# GPU_11_Bit_Counter.net
KiCad netlist of a schematic drawn in EAGLE
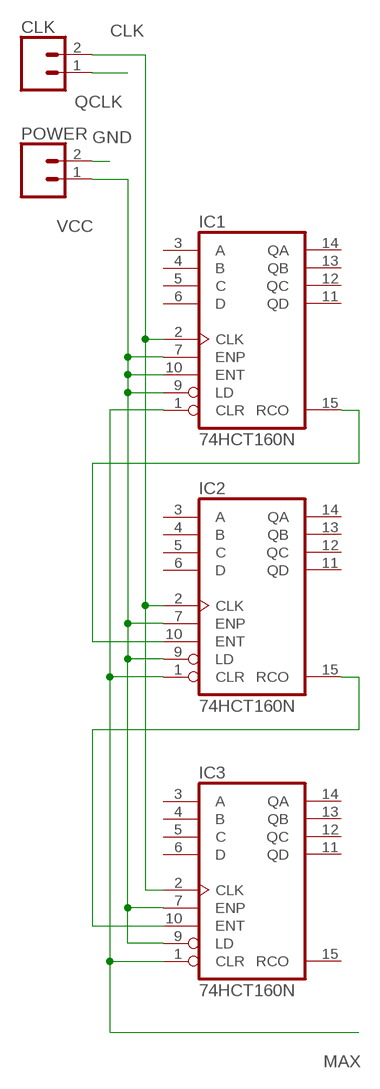
[diagram p0: schematic, sheet 1]

(export (version "E")
  (design (tool "Eeschema 10.0.6"))
  (components
    (comp (ref "CLK")
      (value "CONN_02POGO_PIN_HOLES_ONLY")
      (footprint "eagle-import:1X02_PP_HOLES_ONLY")
      (libsource (lib "eagle-import") (part "CONN_02POGO_PIN_HOLES_ONLY"))
    )
    (comp (ref "IC1")
      (value "74HCT160N")
      (footprint "eagle-import:DIL16")
      (libsource (lib "eagle-import") (part "74160NHCT"))
    )
    (comp (ref "IC2")
      (value "74HCT160N")
      (footprint "eagle-import:DIL16")
      (libsource (lib "eagle-import") (part "74160NHCT"))
    )
    (comp (ref "IC3")
      (value "74HCT160N")
      (footprint "eagle-import:DIL16")
      (libsource (lib "eagle-import") (part "74160NHCT"))
    )
    (comp (ref "POWER")
      (value "CONN_02POGO_PIN_HOLES_ONLY")
      (footprint "eagle-import:1X02_PP_HOLES_ONLY")
      (libsource (lib "eagle-import") (part "CONN_02POGO_PIN_HOLES_ONLY"))
    )
  )
  (nets
    (net (code "1") (name "/CLK") (class "Default")
      (node (ref "CLK") (pin "2") (pinfunction "2_2") (pintype "passive"))
      (node (ref "IC1") (pin "2") (pinfunction "CLK_2") (pintype "input"))
      (node (ref "IC2") (pin "2") (pinfunction "CLK_2") (pintype "input"))
      (node (ref "IC3") (pin "2") (pinfunction "CLK_2") (pintype "input"))
    )
    (net (code "2") (name "/GND") (class "Default")
      (node (ref "POWER") (pin "2") (pinfunction "2_2") (pintype "passive"))
    )
    (net (code "3") (name "/MAX") (class "Default")
      (node (ref "IC1") (pin "1") (pinfunction "CLR_1") (pintype "input"))
      (node (ref "IC2") (pin "1") (pinfunction "CLR_1") (pintype "input"))
      (node (ref "IC3") (pin "1") (pinfunction "CLR_1") (pintype "input"))
    )
    (net (code "4") (name "/QCLK") (class "Default")
      (node (ref "CLK") (pin "1") (pinfunction "1_1") (pintype "passive"))
    )
    (net (code "5") (name "/VCC") (class "Default")
      (node (ref "IC1") (pin "10") (pinfunction "ENT_10") (pintype "input"))
      (node (ref "IC1") (pin "7") (pinfunction "ENP_7") (pintype "input"))
      (node (ref "IC1") (pin "9") (pinfunction "LD_9") (pintype "input"))
      (node (ref "IC2") (pin "7") (pinfunction "ENP_7") (pintype "input"))
      (node (ref "IC2") (pin "9") (pinfunction "LD_9") (pintype "input"))
      (node (ref "IC3") (pin "7") (pinfunction "ENP_7") (pintype "input"))
      (node (ref "IC3") (pin "9") (pinfunction "LD_9") (pintype "input"))
      (node (ref "POWER") (pin "1") (pinfunction "1_1") (pintype "passive"))
    )
    (net (code "6") (name "Net-(IC1A-RCO)") (class "Default")
      (node (ref "IC1") (pin "15") (pinfunction "RCO_15") (pintype "output"))
      (node (ref "IC2") (pin "10") (pinfunction "ENT_10") (pintype "input"))
    )
    (net (code "7") (name "Net-(IC2A-RCO)") (class "Default")
      (node (ref "IC2") (pin "15") (pinfunction "RCO_15") (pintype "output"))
      (node (ref "IC3") (pin "10") (pinfunction "ENT_10") (pintype "input"))
    )
    (net (code "8") (name "unconnected-(IC1A-A-Pad3)") (class "Default")
      (node (ref "IC1") (pin "3") (pinfunction "A_3") (pintype "input"))
    )
    (net (code "9") (name "unconnected-(IC1A-B-Pad4)") (class "Default")
      (node (ref "IC1") (pin "4") (pinfunction "B_4") (pintype "input"))
    )
    (net (code "10") (name "unconnected-(IC1A-C-Pad5)") (class "Default")
      (node (ref "IC1") (pin "5") (pinfunction "C_5") (pintype "input"))
    )
    (net (code "11") (name "unconnected-(IC1A-D-Pad6)") (class "Default")
      (node (ref "IC1") (pin "6") (pinfunction "D_6") (pintype "input"))
    )
    (net (code "12") (name "unconnected-(IC1A-QA-Pad14)") (class "Default")
      (node (ref "IC1") (pin "14") (pinfunction "QA_14") (pintype "output"))
    )
    (net (code "13") (name "unconnected-(IC1A-QB-Pad13)") (class "Default")
      (node (ref "IC1") (pin "13") (pinfunction "QB_13") (pintype "output"))
    )
    (net (code "14") (name "unconnected-(IC1A-QC-Pad12)") (class "Default")
      (node (ref "IC1") (pin "12") (pinfunction "QC_12") (pintype "output"))
    )
    (net (code "15") (name "unconnected-(IC1A-QD-Pad11)") (class "Default")
      (node (ref "IC1") (pin "11") (pinfunction "QD_11") (pintype "output"))
    )
    (net (code "16") (name "unconnected-(IC2A-A-Pad3)") (class "Default")
      (node (ref "IC2") (pin "3") (pinfunction "A_3") (pintype "input"))
    )
    (net (code "17") (name "unconnected-(IC2A-B-Pad4)") (class "Default")
      (node (ref "IC2") (pin "4") (pinfunction "B_4") (pintype "input"))
    )
    (net (code "18") (name "unconnected-(IC2A-C-Pad5)") (class "Default")
      (node (ref "IC2") (pin "5") (pinfunction "C_5") (pintype "input"))
    )
    (net (code "19") (name "unconnected-(IC2A-D-Pad6)") (class "Default")
      (node (ref "IC2") (pin "6") (pinfunction "D_6") (pintype "input"))
    )
    (net (code "20") (name "unconnected-(IC2A-QA-Pad14)") (class "Default")
      (node (ref "IC2") (pin "14") (pinfunction "QA_14") (pintype "output"))
    )
    (net (code "21") (name "unconnected-(IC2A-QB-Pad13)") (class "Default")
      (node (ref "IC2") (pin "13") (pinfunction "QB_13") (pintype "output"))
    )
    (net (code "22") (name "unconnected-(IC2A-QC-Pad12)") (class "Default")
      (node (ref "IC2") (pin "12") (pinfunction "QC_12") (pintype "output"))
    )
    (net (code "23") (name "unconnected-(IC2A-QD-Pad11)") (class "Default")
      (node (ref "IC2") (pin "11") (pinfunction "QD_11") (pintype "output"))
    )
    (net (code "24") (name "unconnected-(IC3A-A-Pad3)") (class "Default")
      (node (ref "IC3") (pin "3") (pinfunction "A_3") (pintype "input"))
    )
    (net (code "25") (name "unconnected-(IC3A-B-Pad4)") (class "Default")
      (node (ref "IC3") (pin "4") (pinfunction "B_4") (pintype "input"))
    )
    (net (code "26") (name "unconnected-(IC3A-C-Pad5)") (class "Default")
      (node (ref "IC3") (pin "5") (pinfunction "C_5") (pintype "input"))
    )
    (net (code "27") (name "unconnected-(IC3A-D-Pad6)") (class "Default")
      (node (ref "IC3") (pin "6") (pinfunction "D_6") (pintype "input"))
    )
    (net (code "28") (name "unconnected-(IC3A-QA-Pad14)") (class "Default")
      (node (ref "IC3") (pin "14") (pinfunction "QA_14") (pintype "output"))
    )
    (net (code "29") (name "unconnected-(IC3A-QB-Pad13)") (class "Default")
      (node (ref "IC3") (pin "13") (pinfunction "QB_13") (pintype "output"))
    )
    (net (code "30") (name "unconnected-(IC3A-QC-Pad12)") (class "Default")
      (node (ref "IC3") (pin "12") (pinfunction "QC_12") (pintype "output"))
    )
    (net (code "31") (name "unconnected-(IC3A-QD-Pad11)") (class "Default")
      (node (ref "IC3") (pin "11") (pinfunction "QD_11") (pintype "output"))
    )
    (net (code "32") (name "unconnected-(IC3A-RCO-Pad15)") (class "Default")
      (node (ref "IC3") (pin "15") (pinfunction "RCO_15") (pintype "output"))
    )
  )
)
